# LM393.net
KiCad netlist of a schematic drawn in Altium Designer
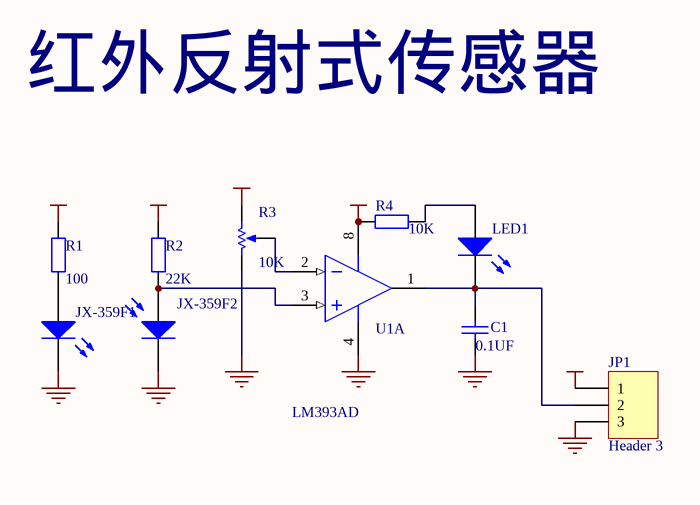
[diagram p0: 红外反射LM393.SchDoc]

(export (version "E")
  (design (tool "Eeschema 10.0.6"))
  (components
    (comp (ref "C1")
      (value "0.1UF")
      (footprint "C1608-0603")
      (description "Capacitor (Semiconductor SIM Model)")
      (fields (field (name "PUBLISHER") "Altium Limited"))
      (libsource (lib "Miscellaneous Devices") (part "Cap Semi"))
    )
    (comp (ref "JP1")
      (value "Header 3")
      (footprint "HDR1X3")
      (description "Header, 3-Pin")
      (fields (field (name "PUBLISHER") "Altium Limited"))
      (libsource (lib "Miscellaneous Connectors") (part "Header 3"))
    )
    (comp (ref "JX-359F1")
      (value "~")
      (footprint "HDR1X2")
      (description "Typical BLUE SiC LED")
      (fields (field (name "PUBLISHER") "Altium Limited"))
      (libsource (lib "Miscellaneous Devices") (part "LED3"))
    )
    (comp (ref "JX-359F2")
      (value "~")
      (footprint "HDR1X2")
      (description "Photosensitive Diode")
      (fields (field (name "PUBLISHER") "Altium Limited"))
      (libsource (lib "Miscellaneous Devices") (part "Photo Sen"))
    )
    (comp (ref "LED1")
      (value "~")
      (footprint "HDR1X2")
      (description "Typical BLUE SiC LED")
      (fields (field (name "PUBLISHER") "Altium Limited"))
      (libsource (lib "Miscellaneous Devices") (part "LED3"))
    )
    (comp (ref "R1")
      (value "100")
      (footprint "C1608-0603")
      (description "Resistor")
      (fields (field (name "PUBLISHER") "Altium Limited"))
      (libsource (lib "") (part "Res2_1"))
    )
    (comp (ref "R2")
      (value "22K")
      (footprint "C1608-0603")
      (description "Resistor")
      (fields (field (name "PUBLISHER") "Altium Limited"))
      (libsource (lib "") (part "Res2_1"))
    )
    (comp (ref "R3")
      (value "10K")
      (footprint "HDR1X3")
      (description "Potentiometer")
      (fields (field (name "PUBLISHER") "Altium Limited"))
      (libsource (lib "Miscellaneous Devices") (part "RPot"))
    )
    (comp (ref "R4")
      (value "10K")
      (footprint "C1608-0603")
      (description "Resistor")
      (fields (field (name "PUBLISHER") "Altium Limited"))
      (libsource (lib "Miscellaneous Devices") (part "Res2"))
    )
    (comp (ref "U1")
      (value "LM393AD")
      (footprint "SO8")
      (description "Low-Power Dual Voltage Comparator")
      (fields (field (name "PUBLISHER") "Altium Limited"))
      (libsource (lib "ST Analog Comparator") (part "LM393AD"))
    )
  )
  (nets
    (net (code "1") (name "GND") (class "Default")
      (node (ref "C1") (pin "1") (pinfunction "1_1") (pintype "passive"))
      (node (ref "JP1") (pin "3") (pinfunction "3_3") (pintype "passive"))
      (node (ref "JX-359F1") (pin "2") (pinfunction "K_2") (pintype "passive"))
      (node (ref "JX-359F2") (pin "2") (pinfunction "K_2") (pintype "passive"))
      (node (ref "R3") (pin "2") (pinfunction "BOT_2") (pintype "passive"))
      (node (ref "U1") (pin "4") (pinfunction "V-_4") (pintype "power_in"))
    )
    (net (code "2") (name "Net-(JX-359F1-A)") (class "Default")
      (node (ref "JX-359F1") (pin "1") (pinfunction "A_1") (pintype "passive"))
      (node (ref "R1") (pin "1") (pinfunction "1_1") (pintype "passive"))
    )
    (net (code "3") (name "Net-(JX-359F2-A)") (class "Default")
      (node (ref "JX-359F2") (pin "1") (pinfunction "A_1") (pintype "passive"))
      (node (ref "R2") (pin "1") (pinfunction "1_1") (pintype "passive"))
      (node (ref "U1") (pin "3") (pinfunction "IN+_3") (pintype "input"))
    )
    (net (code "4") (name "Net-(LED1-A)") (class "Default")
      (node (ref "LED1") (pin "1") (pinfunction "A_1") (pintype "passive"))
      (node (ref "R4") (pin "1") (pinfunction "1_1") (pintype "passive"))
    )
    (net (code "5") (name "Net-(LED1-K)") (class "Default")
      (node (ref "C1") (pin "2") (pinfunction "2_2") (pintype "passive"))
      (node (ref "JP1") (pin "2") (pinfunction "2_2") (pintype "passive"))
      (node (ref "LED1") (pin "2") (pinfunction "K_2") (pintype "passive"))
      (node (ref "U1") (pin "1") (pinfunction "OUT_1") (pintype "open_collector"))
    )
    (net (code "6") (name "Net-(R3-TAP)") (class "Default")
      (node (ref "R3") (pin "3") (pinfunction "TAP_3") (pintype "passive"))
      (node (ref "U1") (pin "2") (pinfunction "IN-_2") (pintype "input"))
    )
    (net (code "7") (name "VCC") (class "Default")
      (node (ref "JP1") (pin "1") (pinfunction "1_1") (pintype "passive"))
      (node (ref "R1") (pin "2") (pinfunction "2_2") (pintype "passive"))
      (node (ref "R2") (pin "2") (pinfunction "2_2") (pintype "passive"))
      (node (ref "R3") (pin "1") (pinfunction "TOP_1") (pintype "passive"))
      (node (ref "R4") (pin "2") (pinfunction "2_2") (pintype "passive"))
      (node (ref "U1") (pin "8") (pinfunction "V+_8") (pintype "power_in"))
    )
  )
)
